# 02_-_POWER.net
KiCad netlist of a schematic drawn in Altium Designer
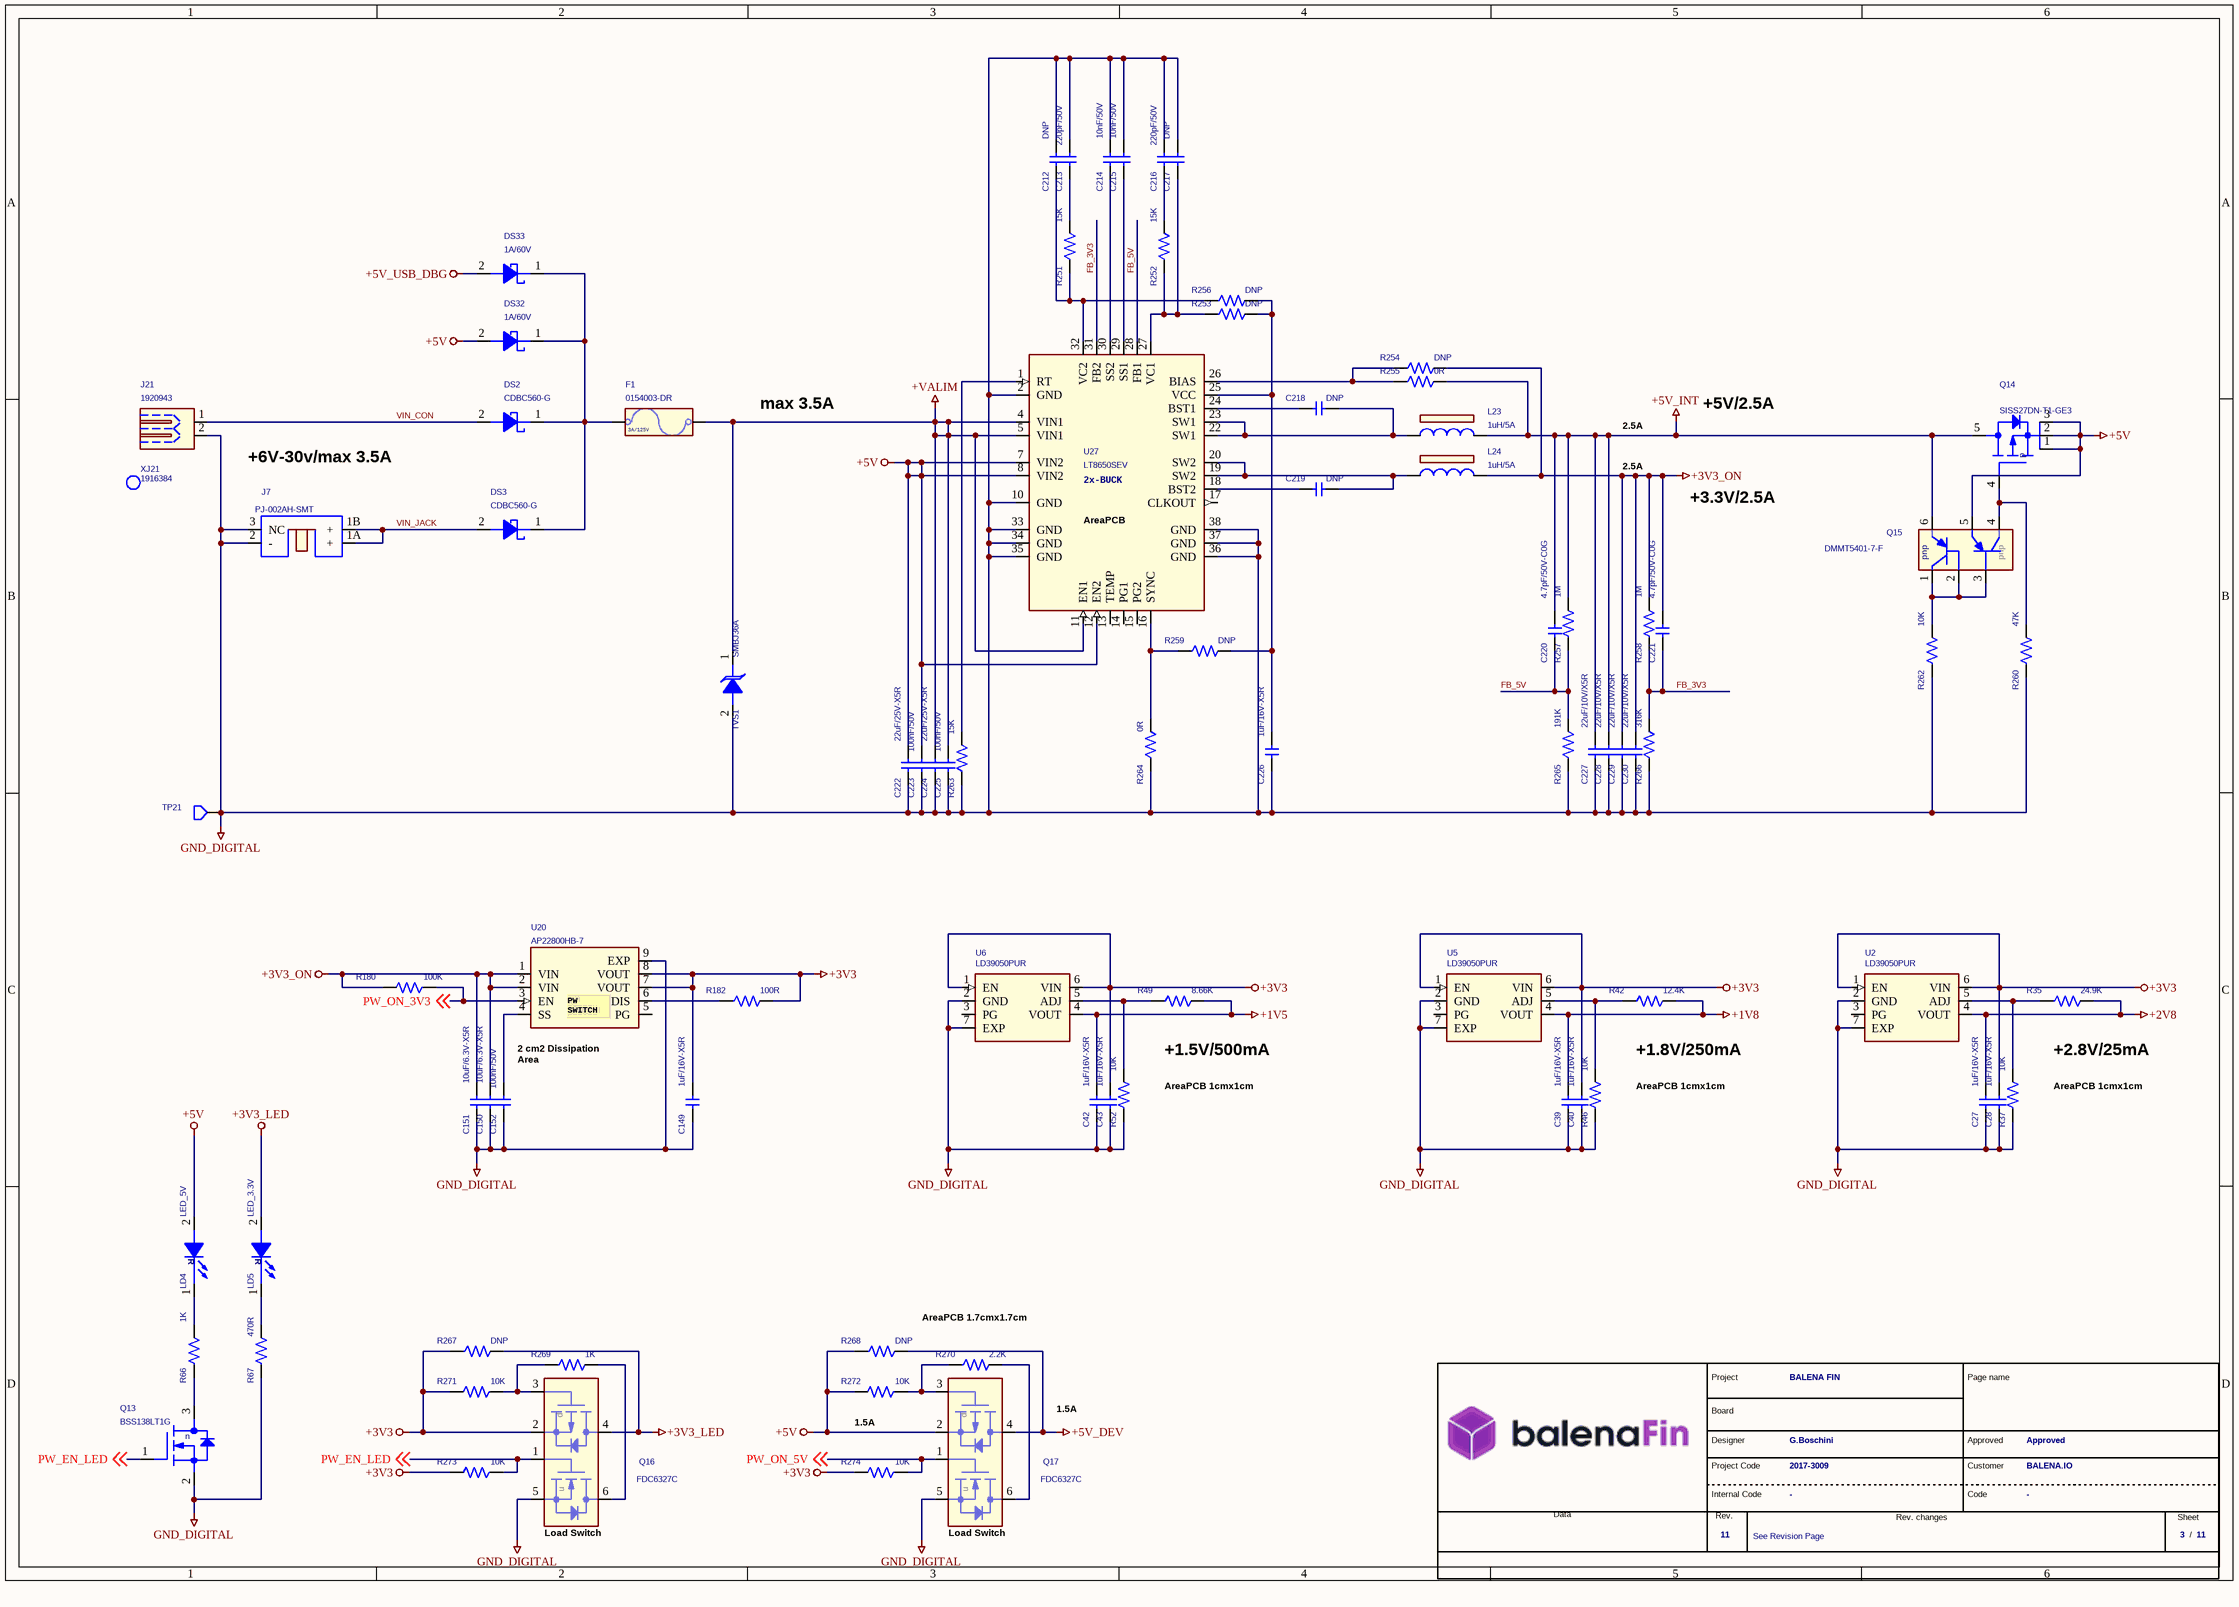
[diagram p0: 02 - POWER.SchDoc]

(export (version "E")
  (design (tool "Eeschema 10.0.6"))
  (components
    (comp (ref "C27")
      (value "1uF/16V-X5R")
      (footprint "CS-C-0402")
      (description "CHIP CAP.CER. 1uF 16V 10% X5R 0402")
      (fields (field (name "MPN") "Generic"))
      (libsource (lib "*") (part "CS-C-0402-1u/16-X5R"))
    )
    (comp (ref "C28")
      (value "1uF/16V-X5R")
      (footprint "CS-C-0402")
      (description "CHIP CAP.CER. 1uF 16V 10% X5R 0402")
      (fields (field (name "MPN") "Generic"))
      (libsource (lib "*") (part "CS-C-0402-1u/16-X5R"))
    )
    (comp (ref "C39")
      (value "1uF/16V-X5R")
      (footprint "CS-C-0402")
      (description "CHIP CAP.CER. 1uF 16V 10% X5R 0402")
      (fields (field (name "MPN") "Generic"))
      (libsource (lib "*") (part "CS-C-0402-1u/16-X5R"))
    )
    (comp (ref "C40")
      (value "1uF/16V-X5R")
      (footprint "CS-C-0402")
      (description "CHIP CAP.CER. 1uF 16V 10% X5R 0402")
      (fields (field (name "MPN") "Generic"))
      (libsource (lib "*") (part "CS-C-0402-1u/16-X5R"))
    )
    (comp (ref "C42")
      (value "1uF/16V-X5R")
      (footprint "CS-C-0402")
      (description "CHIP CAP.CER. 1uF 16V 10% X5R 0402")
      (fields (field (name "MPN") "Generic"))
      (libsource (lib "*") (part "CS-C-0402-1u/16-X5R"))
    )
    (comp (ref "C43")
      (value "1uF/16V-X5R")
      (footprint "CS-C-0402")
      (description "CHIP CAP.CER. 1uF 16V 10% X5R 0402")
      (fields (field (name "MPN") "Generic"))
      (libsource (lib "*") (part "CS-C-0402-1u/16-X5R"))
    )
    (comp (ref "C149")
      (value "1uF/16V-X5R")
      (footprint "CS-C-0402")
      (description "CHIP CAP.CER. 1uF 16V 10% X5R 0402")
      (fields (field (name "MPN") "Generic"))
      (libsource (lib "*") (part "CS-C-0402-1u/16-X5R"))
    )
    (comp (ref "C150")
      (value "10uF/6.3V-X5R")
      (footprint "CS-C-0402")
      (description "CHIP CAP.CER. 10uF 6.3V 20% X5R 0402")
      (fields (field (name "MPN") "Generic"))
      (libsource (lib "*") (part "CS-C-0402-10u/6V3-X5R"))
    )
    (comp (ref "C151")
      (value "10uF/6.3V-X5R")
      (footprint "CS-C-0402")
      (description "CHIP CAP.CER. 10uF 6.3V 20% X5R 0402")
      (fields (field (name "MPN") "Generic"))
      (libsource (lib "*") (part "CS-C-0402-10u/6V3-X5R"))
    )
    (comp (ref "C152")
      (value "100nF/50V")
      (footprint "CS-C-0402")
      (description "CHIP CAP.CER. 100nF 16V 10% X7R 0402")
      (fields (field (name "MPN") "Generic"))
      (libsource (lib "*") (part "CS-C-0402-100n/16V"))
    )
    (comp (ref "C212")
      (value "DNP")
      (footprint "CS-C-0402")
      (description "CHIP CAP.CER. 0402")
      (fields (field (name "MPN") "Generic"))
      (libsource (lib "*") (part "CS-C-0402"))
    )
    (comp (ref "C213")
      (value "220pF/50V")
      (footprint "CS-C-0402")
      (description "CHIP CAP.CER. 220pF 50V 10% X7R 0402")
      (fields (field (name "MPN") "Generic"))
      (libsource (lib "*") (part "CS-C-0402-220p/50V"))
    )
    (comp (ref "C214")
      (value "10nF/50V")
      (footprint "CS-C-0402")
      (description "CHIP CAP.CER. 10nF 50V 10% X7R 0402")
      (fields (field (name "MPN") "Generic"))
      (libsource (lib "*") (part "CS-C-0402-10n/50V"))
    )
    (comp (ref "C215")
      (value "10nF/50V")
      (footprint "CS-C-0402")
      (description "CHIP CAP.CER. 10nF 50V 10% X7R 0402")
      (fields (field (name "MPN") "Generic"))
      (libsource (lib "*") (part "CS-C-0402-10n/50V"))
    )
    (comp (ref "C216")
      (value "220pF/50V")
      (footprint "CS-C-0402")
      (description "CHIP CAP.CER. 220pF 50V 10% X7R 0402")
      (fields (field (name "MPN") "Generic"))
      (libsource (lib "*") (part "CS-C-0402-220p/50V"))
    )
    (comp (ref "C217")
      (value "DNP")
      (footprint "CS-C-0402")
      (description "CHIP CAP.CER. 0402")
      (fields (field (name "MPN") "Generic"))
      (libsource (lib "*") (part "CS-C-0402"))
    )
    (comp (ref "C218")
      (value "DNP")
      (footprint "CS-C-0402")
      (description "CHIP CAP.CER. 0402")
      (fields (field (name "MPN") "Generic"))
      (libsource (lib "*") (part "CS-C-0402"))
    )
    (comp (ref "C219")
      (value "DNP")
      (footprint "CS-C-0402")
      (description "CHIP CAP.CER. 0402")
      (fields (field (name "MPN") "Generic"))
      (libsource (lib "*") (part "CS-C-0402"))
    )
    (comp (ref "C220")
      (value "4.7pF/50V-C0G")
      (footprint "CS-C-0402")
      (description "CHIP CAP.CER. 4.7pF 50V 5% C0G 0402")
      (fields (field (name "MPN") "Generic"))
      (libsource (lib "*") (part "CS-C-0402-4.7p/50V-C0G"))
    )
    (comp (ref "C221")
      (value "4.7pF/50V-C0G")
      (footprint "CS-C-0402")
      (description "CHIP CAP.CER. 4.7pF 50V 5% C0G 0402")
      (fields (field (name "MPN") "Generic"))
      (libsource (lib "*") (part "CS-C-0402-4.7p/50V-C0G"))
    )
    (comp (ref "C222")
      (value "22uF/25V-X5R")
      (footprint "CS-C-1206")
      (description "CHIP CAP.CER. 22uF 25V 10% X5R 1206")
      (fields (field (name "MPN") "Generic"))
      (libsource (lib "*") (part "CS-C-1206-22u/25V-X5R"))
    )
    (comp (ref "C223")
      (value "100nF/50V")
      (footprint "CS-C-0603")
      (description "CHIP CAP.CER. 100nF 50V 10% X7R 0603")
      (fields (field (name "MPN") "Generic"))
      (libsource (lib "*") (part "CS-C-0603-100n/50V"))
    )
    (comp (ref "C224")
      (value "22uF/25V-X5R")
      (footprint "CS-C-1206")
      (description "CHIP CAP.CER. 22uF 25V 10% X5R 1206")
      (fields (field (name "MPN") "Generic"))
      (libsource (lib "*") (part "CS-C-1206-22u/25V-X5R"))
    )
    (comp (ref "C225")
      (value "100nF/50V")
      (footprint "CS-C-0603")
      (description "CHIP CAP.CER. 100nF 50V 10% X7R 0603")
      (fields (field (name "MPN") "Generic"))
      (libsource (lib "*") (part "CS-C-0603-100n/50V"))
    )
    (comp (ref "C226")
      (value "1uF/16V-X5R")
      (footprint "CS-C-0402")
      (description "CHIP CAP.CER. 1uF 16V 10% X5R 0402")
      (fields (field (name "MPN") "Generic"))
      (libsource (lib "*") (part "CS-C-0402-1u/16-X5R"))
    )
    (comp (ref "C227")
      (value "22uF/10V/X5R")
      (footprint "CS-C-0603")
      (description "CHIP CAP.CER. 22uF 10V 20% X5R 0603")
      (fields (field (name "MPN") "Generic"))
      (libsource (lib "*") (part "CS-C-0603-22u/10V/X5R"))
    )
    (comp (ref "C228")
      (value "22uF/10V/X5R")
      (footprint "CS-C-0603")
      (description "CHIP CAP.CER. 22uF 10V 20% X5R 0603")
      (fields (field (name "MPN") "Generic"))
      (libsource (lib "*") (part "CS-C-0603-22u/10V/X5R"))
    )
    (comp (ref "C229")
      (value "22uF/10V/X5R")
      (footprint "CS-C-0603")
      (description "CHIP CAP.CER. 22uF 10V 20% X5R 0603")
      (fields (field (name "MPN") "Generic"))
      (libsource (lib "*") (part "CS-C-0603-22u/10V/X5R"))
    )
    (comp (ref "C230")
      (value "22uF/10V/X5R")
      (footprint "CS-C-0603")
      (description "CHIP CAP.CER. 22uF 10V 20% X5R 0603")
      (fields (field (name "MPN") "Generic"))
      (libsource (lib "*") (part "CS-C-0603-22u/10V/X5R"))
    )
    (comp (ref "DS2")
      (value "CDBC560-G")
      (footprint "SMC")
      (description "DIODE SCHOTTKY 5A 60V CDBC560-G DO214AB SMT")
      (libsource (lib "*") (part "SCHOTTKY-CDBC560-G - 5A/60V"))
    )
    (comp (ref "DS3")
      (value "CDBC560-G")
      (footprint "SMC")
      (description "DIODE SCHOTTKY 5A 60V CDBC560-G DO214AB SMT")
      (libsource (lib "*") (part "SCHOTTKY-CDBC560-G - 5A/60V"))
    )
    (comp (ref "DS32")
      (value "1A/60V")
      (footprint "SMA")
      (description "DIODE SCHOTTKY 1A 60V MBRA160T3G SMA SMT")
      (fields (field (name "MPN") "MBRA160T3G"))
      (libsource (lib "*") (part "SCHOTTKY-MBRA160 - 1A/60V"))
    )
    (comp (ref "DS33")
      (value "1A/60V")
      (footprint "SMA")
      (description "DIODE SCHOTTKY 1A 60V MBRA160T3G SMA SMT")
      (fields (field (name "MPN") "MBRA160T3G"))
      (libsource (lib "*") (part "SCHOTTKY-MBRA160 - 1A/60V"))
    )
    (comp (ref "F1")
      (value "0154003-DR")
      (footprint "F-LT154")
      (description "FUSE BOARD MNT 3A 125VAC/VDC SMD")
      (libsource (lib "*") (part "RAPIDO - 0154003.DR - 3A/125V"))
    )
    (comp (ref "J7")
      (value "PJ-002AH-SMT")
      (footprint "J-CUPJ002AH")
      (description "CONN. POWER JACK F/90° PJ-002AH-SMT-TR CUI SMT")
      (libsource (lib "*") (part "JACK-PW - J-CUPJ002AH"))
    )
    (comp (ref "J21")
      (value "1920943")
      (footprint "J-2-0350-MOT-MC")
      (description "TERM BLOCK HDR 2POS 90DEG 3.5MM")
      (libsource (lib "*") (part "MC - J-2-0350-MOT-MC"))
    )
    (comp (ref "L23")
      (value "1uH/5A")
      (footprint "LS-VIIHLP1212BZ11")
      (description "FIXED IND 1UH 5A 24 MOHM SMD")
      (fields (field (name "MPN") "IHLP1212BZER1R0M11"))
      (libsource (lib "*") (part "PW-IHLP1212BZER1R0M11-1u/5A"))
    )
    (comp (ref "L24")
      (value "1uH/5A")
      (footprint "LS-VIIHLP1212BZ11")
      (description "FIXED IND 1UH 5A 24 MOHM SMD")
      (fields (field (name "MPN") "IHLP1212BZER1R0M11"))
      (libsource (lib "*") (part "PW-IHLP1212BZER1R0M11-1u/5A"))
    )
    (comp (ref "LD4")
      (value "LED_5V")
      (footprint "LD-0603")
      (description "LED Red 0603 SMT")
      (fields (field (name "MPN") "Generic"))
      (libsource (lib "*") (part "LED R - GENERICO - 0603"))
    )
    (comp (ref "LD5")
      (value "LED_3.3V")
      (footprint "LD-0603")
      (description "LED Red 0603 SMT")
      (fields (field (name "MPN") "Generic"))
      (libsource (lib "*") (part "LED R - GENERICO - 0603"))
    )
    (comp (ref "Q13")
      (value "BSS138LT1G")
      (footprint "SOT23")
      (description "MOSFET N-CH 50V 220MA SOT23-3")
      (libsource (lib "*") (part "NMOS - BSS138 - 0.2A/50V"))
    )
    (comp (ref "Q14")
      (value "SISS27DN-T1-GE3")
      (footprint "POWERVDFN8-0330X0330")
      (description "MOSFET P-CH 30V 50A PPAK 1212-8S")
      (libsource (lib "*") (part "PMOS - SISS27DN - 23A/30V"))
    )
    (comp (ref "Q15")
      (value "DMMT5401-7-F")
      (footprint "SOT23-6L")
      (description "TRANS 2PNP 150V 0.2A SOT26")
      (libsource (lib "*") (part "PNPPNP - DMMT5401-7-F-0.2A/150V"))
    )
    (comp (ref "Q16")
      (value "FDC6327C")
      (footprint "SOT23-6-DBV")
      (description "MOSFET N/P-CH 20V SSOT-6")
      (libsource (lib "*") (part "N-P MOS-FDC6327C-2.7A/1.9A/20V"))
    )
    (comp (ref "Q17")
      (value "FDC6327C")
      (footprint "SOT23-6-DBV")
      (description "MOSFET N/P-CH 20V SSOT-6")
      (libsource (lib "*") (part "N-P MOS-FDC6327C-2.7A/1.9A/20V"))
    )
    (comp (ref "R35")
      (value "24.9K")
      (footprint "RS-0402")
      (description "CHIP RES. 24K9 0402 1/16W 1%")
      (fields (field (name "MPN") "Generic"))
      (libsource (lib "*") (part "RS-0402-24.9k"))
    )
    (comp (ref "R37")
      (value "10K")
      (footprint "RS-0402")
      (description "CHIP RES. 10K 0402 1/16W 1%")
      (fields (field (name "MPN") "Generic"))
      (libsource (lib "*") (part "RS-0402-10k"))
    )
    (comp (ref "R42")
      (value "12.4K")
      (footprint "RS-0402")
      (description "CHIP RES. 12K4 0402 1/16W 1% 100PPM/°C")
      (fields (field (name "MPN") "Generic"))
      (libsource (lib "*") (part "RS-0402-12.4k"))
    )
    (comp (ref "R46")
      (value "10K")
      (footprint "RS-0402")
      (description "CHIP RES. 10K 0402 1/16W 1%")
      (fields (field (name "MPN") "Generic"))
      (libsource (lib "*") (part "RS-0402-10k"))
    )
    (comp (ref "R49")
      (value "8.66K")
      (footprint "RS-0402")
      (description "CHIP RES. 8K66 0402 1/16W 1% 100PPM/°C")
      (fields (field (name "MPN") "Generic"))
      (libsource (lib "*") (part "RS-0402-8.66k"))
    )
    (comp (ref "R52")
      (value "10K")
      (footprint "RS-0402")
      (description "CHIP RES. 10K 0402 1/16W 1%")
      (fields (field (name "MPN") "Generic"))
      (libsource (lib "*") (part "RS-0402-10k"))
    )
    (comp (ref "R66")
      (value "1K")
      (footprint "RS-0402")
      (description "CHIP RES. 1K 0402 1/16W 1%")
      (fields (field (name "MPN") "Generic"))
      (libsource (lib "*") (part "RS-0402-1k"))
    )
    (comp (ref "R67")
      (value "470R")
      (footprint "RS-0402")
      (description "CHIP RES. 470R 0402 1/16W 1%")
      (fields (field (name "MPN") "Generic"))
      (libsource (lib "*") (part "RS-0402-470r"))
    )
    (comp (ref "R180")
      (value "100K")
      (footprint "RS-0402")
      (description "CHIP RES. 100K 0402 1/16W 1%")
      (fields (field (name "MPN") "Generic"))
      (libsource (lib "*") (part "RS-0402-100k"))
    )
    (comp (ref "R182")
      (value "100R")
      (footprint "RS-1206")
      (description "CHIP RES. 100R 1206 1/4W 1%")
      (fields (field (name "MPN") "Generic"))
      (libsource (lib "*") (part "RS-1206-100r"))
    )
    (comp (ref "R251")
      (value "15K")
      (footprint "RS-0402")
      (description "CHIP RES. 15K 0402 1/16W 1%")
      (fields (field (name "MPN") "Generic"))
      (libsource (lib "*") (part "RS-0402-15k"))
    )
    (comp (ref "R252")
      (value "15K")
      (footprint "RS-0402")
      (description "CHIP RES. 15K 0402 1/16W 1%")
      (fields (field (name "MPN") "Generic"))
      (libsource (lib "*") (part "RS-0402-15k"))
    )
    (comp (ref "R253")
      (value "DNP")
      (footprint "RS-0402")
      (description "CHIP RES. 0402")
      (fields (field (name "MPN") "Generic"))
      (libsource (lib "*") (part "RS-0402"))
    )
    (comp (ref "R254")
      (value "DNP")
      (footprint "RS-0402")
      (description "CHIP RES. 0402")
      (fields (field (name "MPN") "Generic"))
      (libsource (lib "*") (part "RS-0402"))
    )
    (comp (ref "R255")
      (value "0R")
      (footprint "RS-0402")
      (description "CHIP RES. 0R 0402 1/16W 1%")
      (fields (field (name "MPN") "Generic"))
      (libsource (lib "*") (part "RS-0402-0r"))
    )
    (comp (ref "R256")
      (value "DNP")
      (footprint "RS-0402")
      (description "CHIP RES. 0402")
      (fields (field (name "MPN") "Generic"))
      (libsource (lib "*") (part "RS-0402"))
    )
    (comp (ref "R257")
      (value "1M")
      (footprint "RS-0402")
      (description "CHIP RES. 1M 0402 1/16W 1%")
      (fields (field (name "MPN") "Generic"))
      (libsource (lib "*") (part "RS-0402-1M"))
    )
    (comp (ref "R258")
      (value "1M")
      (footprint "RS-0402")
      (description "CHIP RES. 1M 0402 1/16W 1%")
      (fields (field (name "MPN") "Generic"))
      (libsource (lib "*") (part "RS-0402-1M"))
    )
    (comp (ref "R259")
      (value "DNP")
      (footprint "RS-0402")
      (description "CHIP RES. 0402")
      (fields (field (name "MPN") "Generic"))
      (libsource (lib "*") (part "RS-0402"))
    )
    (comp (ref "R260")
      (value "47K")
      (footprint "RS-0402")
      (description "CHIP RES. 47K 0402 1/16W 1% 100PPM/°C")
      (fields (field (name "MPN") "Generic"))
      (libsource (lib "*") (part "RS-0402-47k"))
    )
    (comp (ref "R262")
      (value "10K")
      (footprint "RS-0402")
      (description "CHIP RES. 10K 0402 1/16W 1%")
      (fields (field (name "MPN") "Generic"))
      (libsource (lib "*") (part "RS-0402-10k"))
    )
    (comp (ref "R263")
      (value "15K")
      (footprint "RS-0402")
      (description "CHIP RES. 15K 0402 1/16W 1%")
      (fields (field (name "MPN") "Generic"))
      (libsource (lib "*") (part "RS-0402-15k"))
    )
    (comp (ref "R264")
      (value "0R")
      (footprint "RS-0402")
      (description "CHIP RES. 0R 0402 1/16W 1%")
      (fields (field (name "MPN") "Generic"))
      (libsource (lib "*") (part "RS-0402-0r"))
    )
    (comp (ref "R265")
      (value "191K")
      (footprint "RS-0402")
      (description "CHIP RES. 191K 0402 1/16W 1%")
      (fields (field (name "MPN") "Generic"))
      (libsource (lib "*") (part "RS-0402-191k"))
    )
    (comp (ref "R266")
      (value "316K")
      (footprint "RS-0402")
      (description "CHIP RES. 316K 0402 1/16W 1%")
      (fields (field (name "MPN") "Generic"))
      (libsource (lib "*") (part "RS-0402-316k"))
    )
    (comp (ref "R267")
      (value "DNP")
      (footprint "RS-0603")
      (description "CHIP RES. 0603")
      (fields (field (name "MPN") "Generic"))
      (libsource (lib "*") (part "RS-0603"))
    )
    (comp (ref "R268")
      (value "DNP")
      (footprint "RS-0603")
      (description "CHIP RES. 0603")
      (fields (field (name "MPN") "Generic"))
      (libsource (lib "*") (part "RS-0603"))
    )
    (comp (ref "R269")
      (value "1K")
      (footprint "RS-0402")
      (description "CHIP RES. 1K 0402 1/16W 1%")
      (fields (field (name "MPN") "Generic"))
      (libsource (lib "*") (part "RS-0402-1k"))
    )
    (comp (ref "R270")
      (value "2.2K")
      (footprint "RS-0402")
      (description "CHIP RES. 2K2 0402 1/16W 1%")
      (fields (field (name "MPN") "Generic"))
      (libsource (lib "*") (part "RS-0402-2.2k"))
    )
    (comp (ref "R271")
      (value "10K")
      (footprint "RS-0402")
      (description "CHIP RES. 10K 0402 1/16W 1%")
      (fields (field (name "MPN") "Generic"))
      (libsource (lib "*") (part "RS-0402-10k"))
    )
    (comp (ref "R272")
      (value "10K")
      (footprint "RS-0402")
      (description "CHIP RES. 10K 0402 1/16W 1%")
      (fields (field (name "MPN") "Generic"))
      (libsource (lib "*") (part "RS-0402-10k"))
    )
    (comp (ref "R273")
      (value "10K")
      (footprint "RS-0402")
      (description "CHIP RES. 10K 0402 1/16W 1%")
      (fields (field (name "MPN") "Generic"))
      (libsource (lib "*") (part "RS-0402-10k"))
    )
    (comp (ref "R274")
      (value "10K")
      (footprint "RS-0402")
      (description "CHIP RES. 10K 0402 1/16W 1%")
      (fields (field (name "MPN") "Generic"))
      (libsource (lib "*") (part "RS-0402-10k"))
    )
    (comp (ref "TP21")
      (value "TPT")
      (footprint "TPT-0100")
      (description "PCB Test Point, Black, - Through Hole Mount, 1.02 mm, Phosphor Bronze, Tin Plated Contacts")
      (fields (field (name "MPN") "20-2137"))
      (libsource (lib "*") (part "TEST POINT THT - 2.2MM"))
    )
    (comp (ref "TVS1")
      (value "SMBJ36A")
      (footprint "SMB")
      (description "TVS DIODE 36VWM 58.1VC SMB")
      (libsource (lib "*") (part "TVS-UNI - SMBJ36A - 36V/600W"))
    )
    (comp (ref "U2")
      (value "LD39050PUR")
      (footprint "DFN6_3X3_STM-L")
      (description "Linear Voltage Regulator IC Positive Adjustable 1 Output 500mA 6-DFN (3x3)")
      (libsource (lib "*") (part "LDO - LD39050PUR - 0.5A/ADJ"))
    )
    (comp (ref "U5")
      (value "LD39050PUR")
      (footprint "DFN6_3X3_STM-L")
      (description "Linear Voltage Regulator IC Positive Adjustable 1 Output 500mA 6-DFN (3x3)")
      (libsource (lib "*") (part "LDO - LD39050PUR - 0.5A/ADJ"))
    )
    (comp (ref "U6")
      (value "LD39050PUR")
      (footprint "DFN6_3X3_STM-L")
      (description "Linear Voltage Regulator IC Positive Adjustable 1 Output 500mA 6-DFN (3x3)")
      (libsource (lib "*") (part "LDO - LD39050PUR - 0.5A/ADJ"))
    )
    (comp (ref "U20")
      (value "AP22800HB-7")
      (footprint "UFDFN8-EXP-0210X0160")
      (description "IC PWR SWITCH N-CHAN 1:1 8UDFN")
      (libsource (lib "*") (part "PSW - 1x - AP22800HB-7"))
    )
    (comp (ref "U27")
      (value "LT8650SEV")
      (footprint "IC-LT8650SEV")
      (description "IC REG BCK 3.3V/5V 4A DL 32LQFN")
      (libsource (lib "*") (part "BUCK-2X-LT8650SEV- 4A/ADJ"))
    )
    (comp (ref "XJ21")
      (value "1916384")
      (description "2 Position Terminal Block Plug, Female Sockets 0.138\" (3.50mm) - 180° Free Hanging (In-Line)")
      (libsource (lib "*") (part "MORS.ESTR. - MC-3.50-2P"))
    )
  )
  (nets
    (net (code "1") (name "+1V5") (class "Default")
      (node (ref "C42") (pin "1") (pinfunction "1_1") (pintype "passive"))
      (node (ref "R49") (pin "2") (pinfunction "2_2") (pintype "passive"))
      (node (ref "U6") (pin "4") (pinfunction "VOUT_4") (pintype "power_in"))
    )
    (net (code "2") (name "+1V8") (class "Default")
      (node (ref "C39") (pin "1") (pinfunction "1_1") (pintype "passive"))
      (node (ref "R42") (pin "2") (pinfunction "2_2") (pintype "passive"))
      (node (ref "U5") (pin "4") (pinfunction "VOUT_4") (pintype "power_in"))
    )
    (net (code "3") (name "+2V8") (class "Default")
      (node (ref "C27") (pin "1") (pinfunction "1_1") (pintype "passive"))
      (node (ref "R35") (pin "2") (pinfunction "2_2") (pintype "passive"))
      (node (ref "U2") (pin "4") (pinfunction "VOUT_4") (pintype "power_in"))
    )
    (net (code "4") (name "+3V3") (class "Default")
      (node (ref "C149") (pin "1") (pinfunction "1_1") (pintype "passive"))
      (node (ref "C28") (pin "1") (pinfunction "1_1") (pintype "passive"))
      (node (ref "C40") (pin "1") (pinfunction "1_1") (pintype "passive"))
      (node (ref "C43") (pin "1") (pinfunction "1_1") (pintype "passive"))
      (node (ref "Q16") (pin "2") (pinfunction "S1_2") (pintype "passive"))
      (node (ref "R182") (pin "2") (pinfunction "2_2") (pintype "passive"))
      (node (ref "R267") (pin "1") (pinfunction "1_1") (pintype "passive"))
      (node (ref "R271") (pin "2") (pinfunction "2_2") (pintype "passive"))
      (node (ref "R273") (pin "2") (pinfunction "2_2") (pintype "passive"))
      (node (ref "R274") (pin "2") (pinfunction "2_2") (pintype "passive"))
      (node (ref "U2") (pin "1") (pinfunction "EN_1") (pintype "input"))
      (node (ref "U2") (pin "6") (pinfunction "VIN_6") (pintype "power_in"))
      (node (ref "U20") (pin "7") (pinfunction "VOUT_7") (pintype "power_in"))
      (node (ref "U20") (pin "8") (pinfunction "VOUT_8") (pintype "power_in"))
      (node (ref "U5") (pin "1") (pinfunction "EN_1") (pintype "input"))
      (node (ref "U5") (pin "6") (pinfunction "VIN_6") (pintype "power_in"))
      (node (ref "U6") (pin "1") (pinfunction "EN_1") (pintype "input"))
      (node (ref "U6") (pin "6") (pinfunction "VIN_6") (pintype "power_in"))
    )
    (net (code "5") (name "+3V3_LED") (class "Default")
      (node (ref "LD5") (pin "2") (pinfunction "A_2") (pintype "passive"))
      (node (ref "Q16") (pin "4") (pinfunction "D1_4") (pintype "passive"))
      (node (ref "R267") (pin "2") (pinfunction "2_2") (pintype "passive"))
    )
    (net (code "6") (name "+3V3_ON") (class "Default")
      (node (ref "C150") (pin "1") (pinfunction "1_1") (pintype "passive"))
      (node (ref "C151") (pin "1") (pinfunction "1_1") (pintype "passive"))
      (node (ref "C221") (pin "1") (pinfunction "1_1") (pintype "passive"))
      (node (ref "C229") (pin "1") (pinfunction "1_1") (pintype "passive"))
      (node (ref "C230") (pin "1") (pinfunction "1_1") (pintype "passive"))
      (node (ref "L24") (pin "2") (pinfunction "2_2") (pintype "passive"))
      (node (ref "R180") (pin "2") (pinfunction "2_2") (pintype "passive"))
      (node (ref "R254") (pin "2") (pinfunction "2_2") (pintype "passive"))
      (node (ref "R258") (pin "2") (pinfunction "2_2") (pintype "passive"))
      (node (ref "U20") (pin "1") (pinfunction "VIN_1") (pintype "power_in"))
      (node (ref "U20") (pin "2") (pinfunction "VIN_2") (pintype "power_in"))
    )
    (net (code "7") (name "+5V") (class "Default")
      (node (ref "C222") (pin "1") (pinfunction "1_1") (pintype "passive"))
      (node (ref "C223") (pin "1") (pinfunction "1_1") (pintype "passive"))
      (node (ref "DS32") (pin "2") (pinfunction "A_2") (pintype "passive"))
      (node (ref "LD4") (pin "2") (pinfunction "A_2") (pintype "passive"))
      (node (ref "Q14") (pin "1") (pinfunction "S_1_1") (pintype "passive"))
      (node (ref "Q14") (pin "2") (pinfunction "S_2_2") (pintype "passive"))
      (node (ref "Q14") (pin "3") (pinfunction "S_3_3") (pintype "passive"))
      (node (ref "Q15") (pin "5") (pinfunction "E2_5") (pintype "passive"))
      (node (ref "Q17") (pin "2") (pinfunction "S1_2") (pintype "passive"))
      (node (ref "R268") (pin "1") (pinfunction "1_1") (pintype "passive"))
      (node (ref "R272") (pin "2") (pinfunction "2_2") (pintype "passive"))
      (node (ref "U27") (pin "12") (pinfunction "EN2_12") (pintype "input"))
      (node (ref "U27") (pin "7") (pinfunction "VIN2_7") (pintype "power_in"))
      (node (ref "U27") (pin "8") (pinfunction "VIN2_8") (pintype "power_in"))
    )
    (net (code "8") (name "+5V_DEV") (class "Default")
      (node (ref "Q17") (pin "4") (pinfunction "D1_4") (pintype "passive"))
      (node (ref "R268") (pin "2") (pinfunction "2_2") (pintype "passive"))
    )
    (net (code "9") (name "+5V_INT") (class "Default")
      (node (ref "C220") (pin "1") (pinfunction "1_1") (pintype "passive"))
      (node (ref "C227") (pin "1") (pinfunction "1_1") (pintype "passive"))
      (node (ref "C228") (pin "1") (pinfunction "1_1") (pintype "passive"))
      (node (ref "L23") (pin "2") (pinfunction "2_2") (pintype "passive"))
      (node (ref "Q14") (pin "5") (pinfunction "D_5_5") (pintype "passive"))
      (node (ref "Q15") (pin "6") (pinfunction "E1_6") (pintype "passive"))
      (node (ref "R255") (pin "2") (pinfunction "2_2") (pintype "passive"))
      (node (ref "R257") (pin "2") (pinfunction "2_2") (pintype "passive"))
    )
    (net (code "10") (name "+5V_USB_DBG") (class "Default")
      (node (ref "DS33") (pin "2") (pinfunction "A_2") (pintype "passive"))
    )
    (net (code "11") (name "+VALIM") (class "Default")
      (node (ref "C224") (pin "1") (pinfunction "1_1") (pintype "passive"))
      (node (ref "C225") (pin "1") (pinfunction "1_1") (pintype "passive"))
      (node (ref "F1") (pin "2") (pinfunction "2_2") (pintype "passive"))
      (node (ref "TVS1") (pin "1") (pinfunction "C_1") (pintype "passive"))
      (node (ref "U27") (pin "11") (pinfunction "EN1_11") (pintype "input"))
      (node (ref "U27") (pin "4") (pinfunction "VIN1_4") (pintype "power_in"))
      (node (ref "U27") (pin "5") (pinfunction "VIN1_5") (pintype "power_in"))
    )
    (net (code "12") (name "/FB_3V3") (class "Default")
      (node (ref "C221") (pin "2") (pinfunction "2_2") (pintype "passive"))
      (node (ref "R258") (pin "1") (pinfunction "1_1") (pintype "passive"))
      (node (ref "R266") (pin "2") (pinfunction "2_2") (pintype "passive"))
      (node (ref "U27") (pin "31") (pinfunction "FB2_31") (pintype "passive"))
    )
    (net (code "13") (name "/FB_5V") (class "Default")
      (node (ref "C220") (pin "2") (pinfunction "2_2") (pintype "passive"))
      (node (ref "R257") (pin "1") (pinfunction "1_1") (pintype "passive"))
      (node (ref "R265") (pin "2") (pinfunction "2_2") (pintype "passive"))
      (node (ref "U27") (pin "28") (pinfunction "FB1_28") (pintype "passive"))
    )
    (net (code "14") (name "/VIN_CON") (class "Default")
      (node (ref "DS2") (pin "2") (pinfunction "A_2") (pintype "passive"))
      (node (ref "J21") (pin "1") (pinfunction "1_1") (pintype "passive"))
    )
    (net (code "15") (name "/VIN_JACK") (class "Default")
      (node (ref "DS3") (pin "2") (pinfunction "A_2") (pintype "passive"))
      (node (ref "J7") (pin "1A") (pinfunction "+_1A") (pintype "power_in"))
      (node (ref "J7") (pin "1B") (pinfunction "+_1B") (pintype "power_in"))
    )
    (net (code "16") (name "GND_DIGITAL") (class "Default")
      (node (ref "C149") (pin "2") (pinfunction "2_2") (pintype "passive"))
      (node (ref "C150") (pin "2") (pinfunction "2_2") (pintype "passive"))
      (node (ref "C151") (pin "2") (pinfunction "2_2") (pintype "passive"))
      (node (ref "C152") (pin "2") (pinfunction "2_2") (pintype "passive"))
      (node (ref "C212") (pin "1") (pinfunction "1_1") (pintype "passive"))
      (node (ref "C213") (pin "1") (pinfunction "1_1") (pintype "passive"))
      (node (ref "C214") (pin "1") (pinfunction "1_1") (pintype "passive"))
      (node (ref "C215") (pin "1") (pinfunction "1_1") (pintype "passive"))
      (node (ref "C216") (pin "1") (pinfunction "1_1") (pintype "passive"))
      (node (ref "C217") (pin "1") (pinfunction "1_1") (pintype "passive"))
      (node (ref "C222") (pin "2") (pinfunction "2_2") (pintype "passive"))
      (node (ref "C223") (pin "2") (pinfunction "2_2") (pintype "passive"))
      (node (ref "C224") (pin "2") (pinfunction "2_2") (pintype "passive"))
      (node (ref "C225") (pin "2") (pinfunction "2_2") (pintype "passive"))
      (node (ref "C226") (pin "2") (pinfunction "2_2") (pintype "passive"))
      (node (ref "C227") (pin "2") (pinfunction "2_2") (pintype "passive"))
      (node (ref "C228") (pin "2") (pinfunction "2_2") (pintype "passive"))
      (node (ref "C229") (pin "2") (pinfunction "2_2") (pintype "passive"))
      (node (ref "C230") (pin "2") (pinfunction "2_2") (pintype "passive"))
      (node (ref "C27") (pin "2") (pinfunction "2_2") (pintype "passive"))
      (node (ref "C28") (pin "2") (pinfunction "2_2") (pintype "passive"))
      (node (ref "C39") (pin "2") (pinfunction "2_2") (pintype "passive"))
      (node (ref "C40") (pin "2") (pinfunction "2_2") (pintype "passive"))
      (node (ref "C42") (pin "2") (pinfunction "2_2") (pintype "passive"))
      (node (ref "C43") (pin "2") (pinfunction "2_2") (pintype "passive"))
      (node (ref "J21") (pin "2") (pinfunction "2_2") (pintype "passive"))
      (node (ref "J7") (pin "2") (pinfunction "-_2") (pintype "power_in"))
      (node (ref "J7") (pin "3") (pinfunction "NC_3") (pintype "passive"))
      (node (ref "Q13") (pin "2") (pinfunction "S_2") (pintype "passive"))
      (node (ref "Q16") (pin "5") (pinfunction "S2_5") (pintype "passive"))
      (node (ref "Q17") (pin "5") (pinfunction "S2_5") (pintype "passive"))
      (node (ref "R260") (pin "1") (pinfunction "1_1") (pintype "passive"))
      (node (ref "R262") (pin "1") (pinfunction "1_1") (pintype "passive"))
      (node (ref "R263") (pin "1") (pinfunction "1_1") (pintype "passive"))
      (node (ref "R264") (pin "1") (pinfunction "1_1") (pintype "passive"))
      (node (ref "R265") (pin "1") (pinfunction "1_1") (pintype "passive"))
      (node (ref "R266") (pin "1") (pinfunction "1_1") (pintype "passive"))
      (node (ref "R37") (pin "1") (pinfunction "1_1") (pintype "passive"))
      (node (ref "R46") (pin "1") (pinfunction "1_1") (pintype "passive"))
      (node (ref "R52") (pin "1") (pinfunction "1_1") (pintype "passive"))
      (node (ref "R67") (pin "1") (pinfunction "1_1") (pintype "passive"))
      (node (ref "TP21") (pin "1") (pinfunction "TP_1") (pintype "passive"))
      (node (ref "TVS1") (pin "2") (pinfunction "A_2") (pintype "passive"))
      (node (ref "U2") (pin "2") (pinfunction "GND_2") (pintype "power_in"))
      (node (ref "U2") (pin "7") (pinfunction "EXP_7") (pintype "power_in"))
      (node (ref "U20") (pin "9") (pinfunction "EXP_9") (pintype "passive"))
      (node (ref "U27") (pin "10") (pinfunction "GND_10") (pintype "power_in"))
      (node (ref "U27") (pin "2") (pinfunction "GND_2") (pintype "power_in"))
      (node (ref "U27") (pin "33") (pinfunction "GND_33") (pintype "power_in"))
      (node (ref "U27") (pin "34") (pinfunction "GND_34") (pintype "power_in"))
      (node (ref "U27") (pin "35") (pinfunction "GND_35") (pintype "power_in"))
      (node (ref "U27") (pin "36") (pinfunction "GND_36") (pintype "power_in"))
      (node (ref "U27") (pin "37") (pinfunction "GND_37") (pintype "power_in"))
      (node (ref "U27") (pin "38") (pinfunction "GND_38") (pintype "power_in"))
      (node (ref "U5") (pin "2") (pinfunction "GND_2") (pintype "power_in"))
      (node (ref "U5") (pin "7") (pinfunction "EXP_7") (pintype "power_in"))
      (node (ref "U6") (pin "2") (pinfunction "GND_2") (pintype "power_in"))
      (node (ref "U6") (pin "7") (pinfunction "EXP_7") (pintype "power_in"))
    )
    (net (code "17") (name "Net-(C213-Pad2)") (class "Default")
      (node (ref "C213") (pin "2") (pinfunction "2_2") (pintype "passive"))
      (node (ref "R251") (pin "2") (pinfunction "2_2") (pintype "passive"))
    )
    (net (code "18") (name "Net-(C216-Pad2)") (class "Default")
      (node (ref "C216") (pin "2") (pinfunction "2_2") (pintype "passive"))
      (node (ref "R252") (pin "2") (pinfunction "2_2") (pintype "passive"))
    )
    (net (code "19") (name "Net-(C218-Pad2)") (class "Default")
      (node (ref "C218") (pin "2") (pinfunction "2_2") (pintype "passive"))
      (node (ref "L23") (pin "1") (pinfunction "1_1") (pintype "passive"))
      (node (ref "U27") (pin "22") (pinfunction "SW1_22") (pintype "power_in"))
      (node (ref "U27") (pin "23") (pinfunction "SW1_23") (pintype "power_in"))
    )
    (net (code "20") (name "Net-(C219-Pad2)") (class "Default")
      (node (ref "C219") (pin "2") (pinfunction "2_2") (pintype "passive"))
      (node (ref "L24") (pin "1") (pinfunction "1_1") (pintype "passive"))
      (node (ref "U27") (pin "19") (pinfunction "SW2_19") (pintype "power_in"))
      (node (ref "U27") (pin "20") (pinfunction "SW2_20") (pintype "power_in"))
    )
    (net (code "21") (name "Net-(DS2-C)") (class "Default")
      (node (ref "DS2") (pin "1") (pinfunction "C_1") (pintype "passive"))
      (node (ref "DS3") (pin "1") (pinfunction "C_1") (pintype "passive"))
      (node (ref "DS32") (pin "1") (pinfunction "C_1") (pintype "passive"))
      (node (ref "DS33") (pin "1") (pinfunction "C_1") (pintype "passive"))
      (node (ref "F1") (pin "1") (pinfunction "1_1") (pintype "passive"))
    )
    (net (code "22") (name "Net-(LD4-C)") (class "Default")
      (node (ref "LD4") (pin "1") (pinfunction "C_1") (pintype "passive"))
      (node (ref "R66") (pin "2") (pinfunction "2_2") (pintype "passive"))
    )
    (net (code "23") (name "Net-(LD5-C)") (class "Default")
      (node (ref "LD5") (pin "1") (pinfunction "C_1") (pintype "passive"))
      (node (ref "R67") (pin "2") (pinfunction "2_2") (pintype "passive"))
    )
    (net (code "24") (name "Net-(Q13-D)") (class "Default")
      (node (ref "Q13") (pin "3") (pinfunction "D_3") (pintype "passive"))
      (node (ref "R66") (pin "1") (pinfunction "1_1") (pintype "passive"))
    )
    (net (code "25") (name "Net-(Q14-G)") (class "Default")
      (node (ref "Q14") (pin "4") (pinfunction "G_4") (pintype "passive"))
      (node (ref "Q15") (pin "4") (pinfunction "C2_4") (pintype "passive"))
      (node (ref "R260") (pin "2") (pinfunction "2_2") (pintype "passive"))
    )
    (net (code "26") (name "Net-(Q15-B1)") (class "Default")
      (node (ref "Q15") (pin "1") (pinfunction "C1_1") (pintype "passive"))
      (node (ref "Q15") (pin "2") (pinfunction "B1_2") (pintype "passive"))
      (node (ref "Q15") (pin "3") (pinfunction "B2_3") (pintype "passive"))
      (node (ref "R262") (pin "2") (pinfunction "2_2") (pintype "passive"))
    )
    (net (code "27") (name "Net-(Q16-D2)") (class "Default")
      (node (ref "Q16") (pin "6") (pinfunction "D2_6") (pintype "passive"))
      (node (ref "R269") (pin "2") (pinfunction "2_2") (pintype "passive"))
    )
    (net (code "28") (name "Net-(Q16-G1)") (class "Default")
      (node (ref "Q16") (pin "3") (pinfunction "G1_3") (pintype "passive"))
      (node (ref "R269") (pin "1") (pinfunction "1_1") (pintype "passive"))
      (node (ref "R271") (pin "1") (pinfunction "1_1") (pintype "passive"))
    )
    (net (code "29") (name "Net-(Q17-D2)") (class "Default")
      (node (ref "Q17") (pin "6") (pinfunction "D2_6") (pintype "passive"))
      (node (ref "R270") (pin "2") (pinfunction "2_2") (pintype "passive"))
    )
    (net (code "30") (name "Net-(Q17-G1)") (class "Default")
      (node (ref "Q17") (pin "3") (pinfunction "G1_3") (pintype "passive"))
      (node (ref "R270") (pin "1") (pinfunction "1_1") (pintype "passive"))
      (node (ref "R272") (pin "1") (pinfunction "1_1") (pintype "passive"))
    )
    (net (code "31") (name "Net-(U2-ADJ)") (class "Default")
      (node (ref "R35") (pin "1") (pinfunction "1_1") (pintype "passive"))
      (node (ref "R37") (pin "2") (pinfunction "2_2") (pintype "passive"))
      (node (ref "U2") (pin "5") (pinfunction "ADJ_5") (pintype "passive"))
    )
    (net (code "32") (name "Net-(U5-ADJ)") (class "Default")
      (node (ref "R42") (pin "1") (pinfunction "1_1") (pintype "passive"))
      (node (ref "R46") (pin "2") (pinfunction "2_2") (pintype "passive"))
      (node (ref "U5") (pin "5") (pinfunction "ADJ_5") (pintype "passive"))
    )
    (net (code "33") (name "Net-(U6-ADJ)") (class "Default")
      (node (ref "R49") (pin "1") (pinfunction "1_1") (pintype "passive"))
      (node (ref "R52") (pin "2") (pinfunction "2_2") (pintype "passive"))
      (node (ref "U6") (pin "5") (pinfunction "ADJ_5") (pintype "passive"))
    )
    (net (code "34") (name "Net-(U20-DIS)") (class "Default")
      (node (ref "R182") (pin "1") (pinfunction "1_1") (pintype "passive"))
      (node (ref "U20") (pin "6") (pinfunction "DIS_6") (pintype "power_in"))
    )
    (net (code "35") (name "Net-(U20-SS)") (class "Default")
      (node (ref "C152") (pin "1") (pinfunction "1_1") (pintype "passive"))
      (node (ref "U20") (pin "4") (pinfunction "SS_4") (pintype "passive"))
    )
    (net (code "36") (name "Net-(U27-BIAS)") (class "Default")
      (node (ref "R254") (pin "1") (pinfunction "1_1") (pintype "passive"))
      (node (ref "R255") (pin "1") (pinfunction "1_1") (pintype "passive"))
      (node (ref "U27") (pin "26") (pinfunction "BIAS_26") (pintype "passive"))
    )
    (net (code "37") (name "Net-(U27-BST1)") (class "Default")
      (node (ref "C218") (pin "1") (pinfunction "1_1") (pintype "passive"))
      (node (ref "U27") (pin "24") (pinfunction "BST1_24") (pintype "passive"))
    )
    (net (code "38") (name "Net-(U27-BST2)") (class "Default")
      (node (ref "C219") (pin "1") (pinfunction "1_1") (pintype "passive"))
      (node (ref "U27") (pin "18") (pinfunction "BST2_18") (pintype "passive"))
    )
    (net (code "39") (name "Net-(U27-RT)") (class "Default")
      (node (ref "R263") (pin "2") (pinfunction "2_2") (pintype "passive"))
      (node (ref "U27") (pin "1") (pinfunction "RT_1") (pintype "input"))
    )
    (net (code "40") (name "Net-(U27-SS1)") (class "Default")
      (node (ref "C215") (pin "2") (pinfunction "2_2") (pintype "passive"))
      (node (ref "U27") (pin "29") (pinfunction "SS1_29") (pintype "passive"))
    )
    (net (code "41") (name "Net-(U27-SS2)") (class "Default")
      (node (ref "C214") (pin "2") (pinfunction "2_2") (pintype "passive"))
      (node (ref "U27") (pin "30") (pinfunction "SS2_30") (pintype "passive"))
    )
    (net (code "42") (name "Net-(U27-SYNC)") (class "Default")
      (node (ref "R259") (pin "1") (pinfunction "1_1") (pintype "passive"))
      (node (ref "R264") (pin "2") (pinfunction "2_2") (pintype "passive"))
      (node (ref "U27") (pin "16") (pinfunction "SYNC_16") (pintype "passive"))
    )
    (net (code "43") (name "Net-(U27-VC1)") (class "Default")
      (node (ref "C217") (pin "2") (pinfunction "2_2") (pintype "passive"))
      (node (ref "R252") (pin "1") (pinfunction "1_1") (pintype "passive"))
      (node (ref "R253") (pin "1") (pinfunction "1_1") (pintype "passive"))
      (node (ref "U27") (pin "27") (pinfunction "VC1_27") (pintype "passive"))
    )
    (net (code "44") (name "Net-(U27-VC2)") (class "Default")
      (node (ref "C212") (pin "2") (pinfunction "2_2") (pintype "passive"))
      (node (ref "R251") (pin "1") (pinfunction "1_1") (pintype "passive"))
      (node (ref "R256") (pin "1") (pinfunction "1_1") (pintype "passive"))
      (node (ref "U27") (pin "32") (pinfunction "VC2_32") (pintype "passive"))
    )
    (net (code "45") (name "Net-(U27-VCC)") (class "Default")
      (node (ref "C226") (pin "1") (pinfunction "1_1") (pintype "passive"))
      (node (ref "R253") (pin "2") (pinfunction "2_2") (pintype "passive"))
      (node (ref "R256") (pin "2") (pinfunction "2_2") (pintype "passive"))
      (node (ref "R259") (pin "2") (pinfunction "2_2") (pintype "passive"))
      (node (ref "U27") (pin "25") (pinfunction "VCC_25") (pintype "passive"))
    )
    (net (code "46") (name "PW_EN_LED") (class "Default")
      (node (ref "Q13") (pin "1") (pinfunction "G_1") (pintype "passive"))
      (node (ref "Q16") (pin "1") (pinfunction "G2_1") (pintype "passive"))
      (node (ref "R273") (pin "1") (pinfunction "1_1") (pintype "passive"))
    )
    (net (code "47") (name "PW_ON_3V3") (class "Default")
      (node (ref "R180") (pin "1") (pinfunction "1_1") (pintype "passive"))
      (node (ref "U20") (pin "3") (pinfunction "EN_3") (pintype "input"))
    )
    (net (code "48") (name "PW_ON_5V") (class "Default")
      (node (ref "Q17") (pin "1") (pinfunction "G2_1") (pintype "passive"))
      (node (ref "R274") (pin "1") (pinfunction "1_1") (pintype "passive"))
    )
    (net (code "49") (name "unconnected-(U2-PG-Pad3)") (class "Default")
      (node (ref "U2") (pin "3") (pinfunction "PG_3") (pintype "passive"))
    )
    (net (code "50") (name "unconnected-(U5-PG-Pad3)") (class "Default")
      (node (ref "U5") (pin "3") (pinfunction "PG_3") (pintype "passive"))
    )
    (net (code "51") (name "unconnected-(U6-PG-Pad3)") (class "Default")
      (node (ref "U6") (pin "3") (pinfunction "PG_3") (pintype "passive"))
    )
    (net (code "52") (name "unconnected-(U20-PG-Pad5)") (class "Default")
      (node (ref "U20") (pin "5") (pinfunction "PG_5") (pintype "open_collector"))
    )
    (net (code "53") (name "unconnected-(U27-CLKOUT-Pad17)") (class "Default")
      (node (ref "U27") (pin "17") (pinfunction "CLKOUT_17") (pintype "output"))
    )
    (net (code "54") (name "unconnected-(U27-PG1-Pad14)") (class "Default")
      (node (ref "U27") (pin "14") (pinfunction "PG1_14") (pintype "open_collector"))
    )
    (net (code "55") (name "unconnected-(U27-PG2-Pad15)") (class "Default")
      (node (ref "U27") (pin "15") (pinfunction "PG2_15") (pintype "open_collector"))
    )
    (net (code "56") (name "unconnected-(U27-TEMP-Pad13)") (class "Default")
      (node (ref "U27") (pin "13") (pinfunction "TEMP_13") (pintype "passive"))
    )
  )
)
